# heatflow.net
KiCad netlist of a schematic drawn in EAGLE
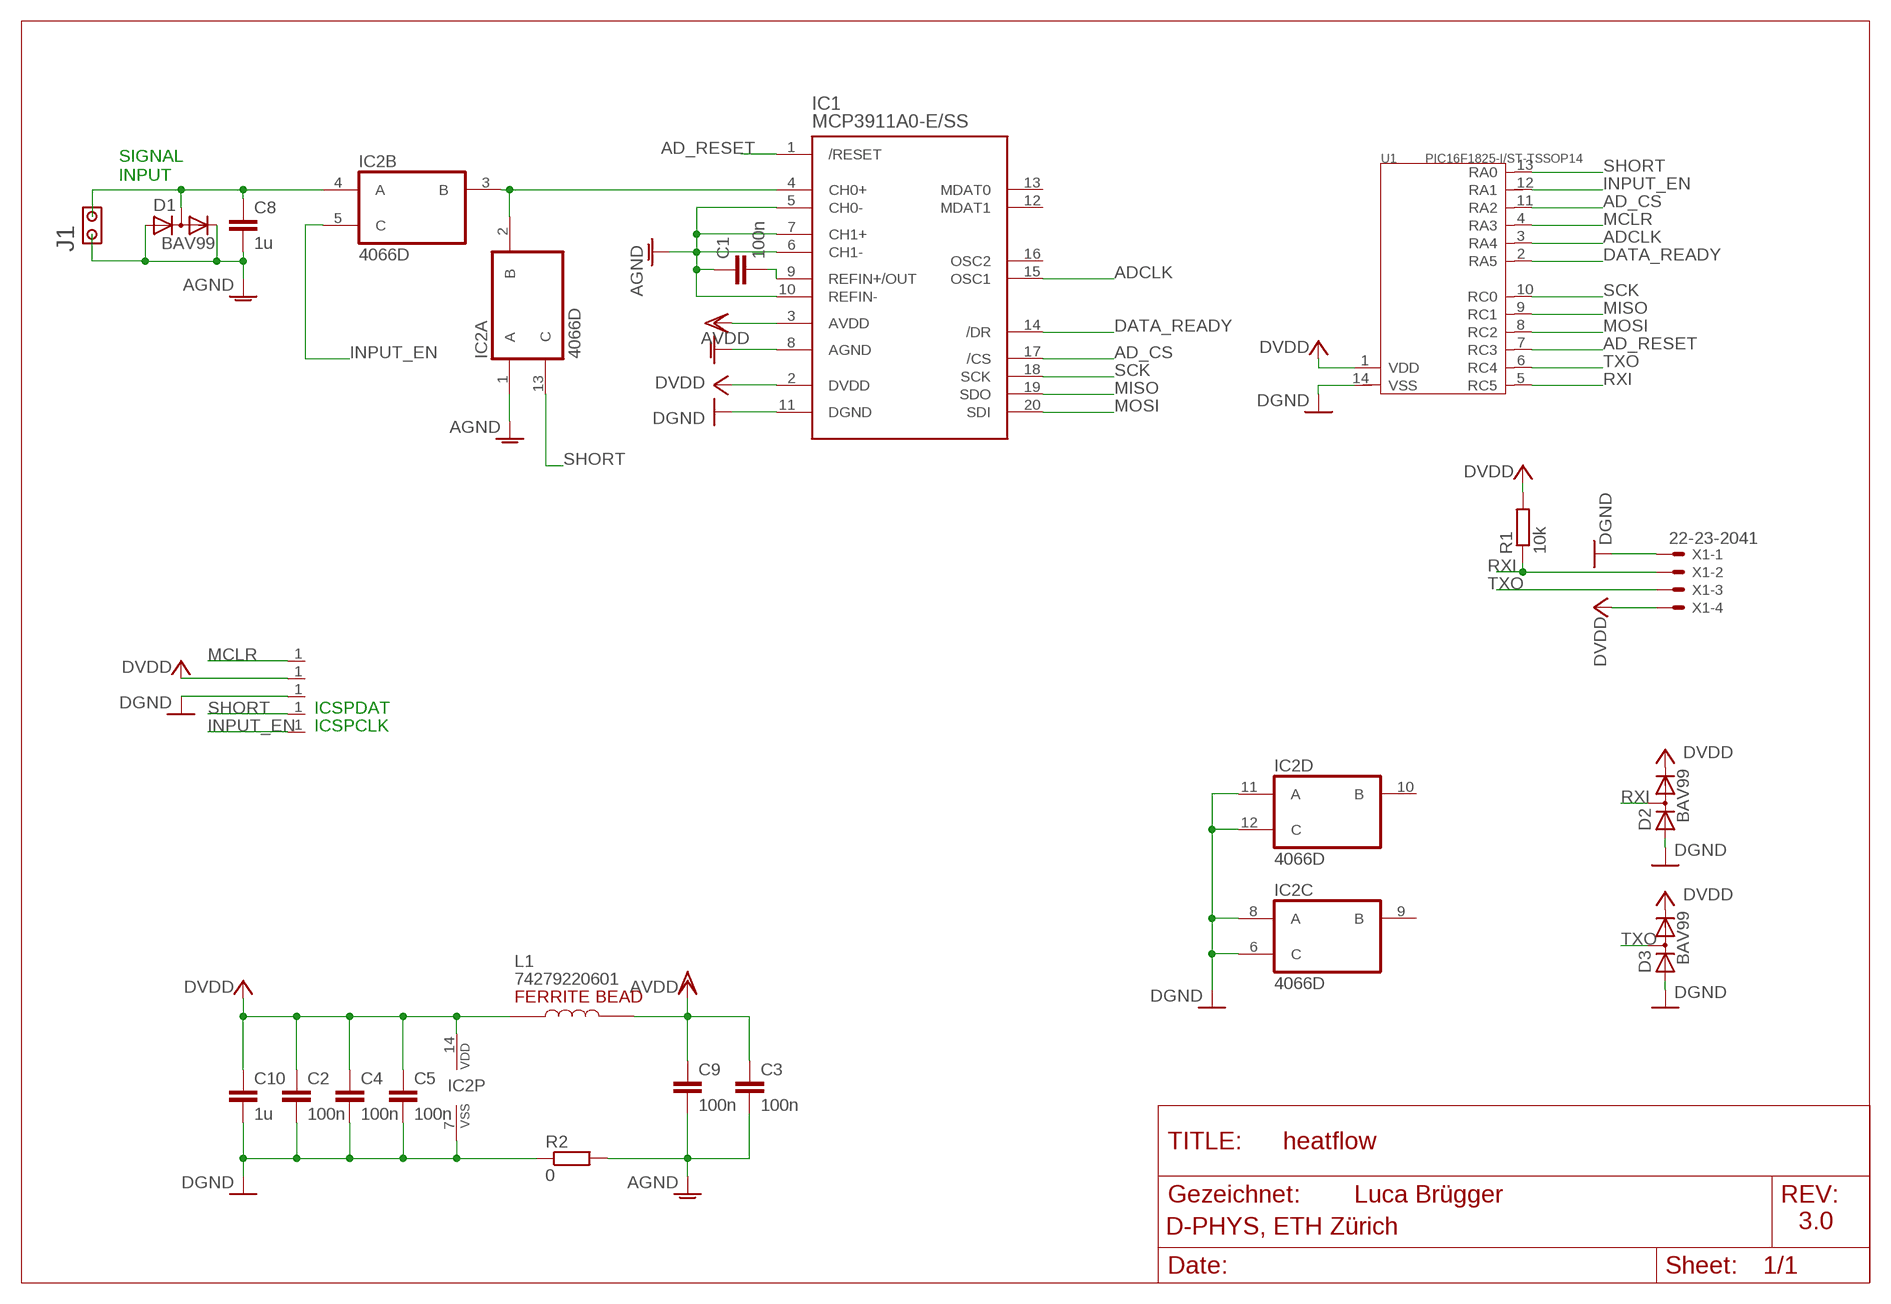
[diagram p0: schematic, sheet 1]

(export (version "E")
  (design (tool "Eeschema 10.0.6"))
  (components
    (comp (ref "C1")
      (value "100n")
      (footprint "eagle-import:C0805")
      (libsource (lib "eagle-import") (part "C-EUC0805"))
    )
    (comp (ref "C2")
      (value "100n")
      (footprint "eagle-import:C0805")
      (libsource (lib "eagle-import") (part "C-EUC0805"))
    )
    (comp (ref "C3")
      (value "100n")
      (footprint "eagle-import:C0805")
      (libsource (lib "eagle-import") (part "C-EUC0805"))
    )
    (comp (ref "C4")
      (value "100n")
      (footprint "eagle-import:C0805")
      (libsource (lib "eagle-import") (part "C-EUC0805"))
    )
    (comp (ref "C5")
      (value "100n")
      (footprint "eagle-import:C0805")
      (libsource (lib "eagle-import") (part "C-EUC0805"))
    )
    (comp (ref "C8")
      (value "1u")
      (footprint "eagle-import:C0805")
      (libsource (lib "eagle-import") (part "C-EUC0805"))
    )
    (comp (ref "C9")
      (value "100n")
      (footprint "eagle-import:C0805")
      (libsource (lib "eagle-import") (part "C-EUC0805"))
    )
    (comp (ref "C10")
      (value "1u")
      (footprint "eagle-import:C0805")
      (libsource (lib "eagle-import") (part "C-EUC0805"))
    )
    (comp (ref "D1")
      (value "BAV99")
      (footprint "eagle-import:SOT23")
      (libsource (lib "eagle-import") (part "BAV99"))
    )
    (comp (ref "D2")
      (value "BAV99")
      (footprint "eagle-import:SOT23")
      (libsource (lib "eagle-import") (part "BAV99"))
    )
    (comp (ref "D3")
      (value "BAV99")
      (footprint "eagle-import:SOT23")
      (libsource (lib "eagle-import") (part "BAV99"))
    )
    (comp (ref "IC1")
      (value "MCP3911A0-E/SS")
      (footprint "eagle-import:SSOP20")
      (libsource (lib "eagle-import") (part "MCP3911A0-E/SS"))
    )
    (comp (ref "IC2")
      (value "4066D")
      (footprint "eagle-import:SO14")
      (libsource (lib "eagle-import") (part "4066D"))
    )
    (comp (ref "J1")
      (value "CON2X1")
      (footprint "eagle-import:CON2X1")
      (libsource (lib "eagle-import") (part "CON2X1"))
    )
    (comp (ref "L1")
      (value "74279220601")
      (footprint "eagle-import:0805")
      (libsource (lib "eagle-import") (part "74279220601"))
    )
    (comp (ref "PIN1")
      (value "CON1X1")
      (footprint "eagle-import:CON1X1")
      (libsource (lib "eagle-import") (part "CON1X1"))
    )
    (comp (ref "PIN2")
      (value "CON1X1")
      (footprint "eagle-import:CON1X1")
      (libsource (lib "eagle-import") (part "CON1X1"))
    )
    (comp (ref "PIN3")
      (value "CON1X1")
      (footprint "eagle-import:CON1X1")
      (libsource (lib "eagle-import") (part "CON1X1"))
    )
    (comp (ref "PIN4")
      (value "CON1X1")
      (footprint "eagle-import:CON1X1")
      (libsource (lib "eagle-import") (part "CON1X1"))
    )
    (comp (ref "PIN5")
      (value "CON1X1")
      (footprint "eagle-import:CON1X1")
      (libsource (lib "eagle-import") (part "CON1X1"))
    )
    (comp (ref "R1")
      (value "10k")
      (footprint "eagle-import:M0805")
      (libsource (lib "eagle-import") (part "R-EU_M0805"))
    )
    (comp (ref "R2")
      (value "0")
      (footprint "eagle-import:M0805")
      (libsource (lib "eagle-import") (part "R-EU_M0805"))
    )
    (comp (ref "U1")
      (value "PIC16F1825-I/ST-TSSOP14")
      (footprint "eagle-import:TSSOP14-0.65-5X4.4MM")
      (fields (field (name "MPN") "PIC16F1825-I/ST"))
      (libsource (lib "eagle-import") (part "MCU-PIC16F1825-I/ST(TSSOP14)"))
    )
    (comp (ref "X1")
      (value "22-23-2041")
      (footprint "eagle-import:22-23-2041")
      (fields (field (name "MF") "MOLEX"))
      (libsource (lib "eagle-import") (part "22-23-2041"))
    )
  )
  (nets
    (net (code "1") (name "/ADCLK") (class "Default")
      (node (ref "IC1") (pin "15") (pinfunction "OSC1_15") (pintype "bidirectional"))
      (node (ref "U1") (pin "3") (pinfunction "RA4_3") (pintype "bidirectional"))
    )
    (net (code "2") (name "/AD_CS") (class "Default")
      (node (ref "IC1") (pin "17") (pinfunction "/CS_17") (pintype "bidirectional"))
      (node (ref "U1") (pin "11") (pinfunction "RA2_11") (pintype "bidirectional"))
    )
    (net (code "3") (name "/AD_RESET") (class "Default")
      (node (ref "IC1") (pin "1") (pinfunction "/RESET_1") (pintype "bidirectional"))
      (node (ref "U1") (pin "7") (pinfunction "RC3_7") (pintype "bidirectional"))
    )
    (net (code "4") (name "/DATA_READY") (class "Default")
      (node (ref "IC1") (pin "14") (pinfunction "/DR_14") (pintype "bidirectional"))
      (node (ref "U1") (pin "2") (pinfunction "RA5_2") (pintype "bidirectional"))
    )
    (net (code "5") (name "/INPUT_EN") (class "Default")
      (node (ref "IC2") (pin "5") (pinfunction "C_5") (pintype "input"))
      (node (ref "PIN5") (pin "1") (pinfunction "1_1") (pintype "passive"))
      (node (ref "U1") (pin "12") (pinfunction "RA1_12") (pintype "bidirectional"))
    )
    (net (code "6") (name "/MCLR") (class "Default")
      (node (ref "PIN1") (pin "1") (pinfunction "1_1") (pintype "passive"))
      (node (ref "U1") (pin "4") (pinfunction "RA3_4") (pintype "bidirectional"))
    )
    (net (code "7") (name "/MISO") (class "Default")
      (node (ref "IC1") (pin "19") (pinfunction "SDO_19") (pintype "bidirectional"))
      (node (ref "U1") (pin "9") (pinfunction "RC1_9") (pintype "bidirectional"))
    )
    (net (code "8") (name "/MOSI") (class "Default")
      (node (ref "IC1") (pin "20") (pinfunction "SDI_20") (pintype "bidirectional"))
      (node (ref "U1") (pin "8") (pinfunction "RC2_8") (pintype "bidirectional"))
    )
    (net (code "9") (name "/RXI") (class "Default")
      (node (ref "D2") (pin "3") (pinfunction "AC_3") (pintype "passive"))
      (node (ref "R1") (pin "1") (pinfunction "1_1") (pintype "passive"))
      (node (ref "U1") (pin "5") (pinfunction "RC5_5") (pintype "bidirectional"))
      (node (ref "X1") (pin "2") (pinfunction "S_2") (pintype "passive"))
    )
    (net (code "10") (name "/SCK") (class "Default")
      (node (ref "IC1") (pin "18") (pinfunction "SCK_18") (pintype "bidirectional"))
      (node (ref "U1") (pin "10") (pinfunction "RC0_10") (pintype "bidirectional"))
    )
    (net (code "11") (name "/SHORT") (class "Default")
      (node (ref "IC2") (pin "13") (pinfunction "C_13") (pintype "input"))
      (node (ref "PIN4") (pin "1") (pinfunction "1_1") (pintype "passive"))
      (node (ref "U1") (pin "13") (pinfunction "RA0_13") (pintype "bidirectional"))
    )
    (net (code "12") (name "/TXO") (class "Default")
      (node (ref "D3") (pin "3") (pinfunction "AC_3") (pintype "passive"))
      (node (ref "U1") (pin "6") (pinfunction "RC4_6") (pintype "bidirectional"))
      (node (ref "X1") (pin "3") (pinfunction "S_3") (pintype "passive"))
    )
    (net (code "13") (name "AGND") (class "Default")
      (node (ref "C1") (pin "1") (pinfunction "1_1") (pintype "passive"))
      (node (ref "C3") (pin "2") (pinfunction "2_2") (pintype "passive"))
      (node (ref "C8") (pin "2") (pinfunction "2_2") (pintype "passive"))
      (node (ref "C9") (pin "2") (pinfunction "2_2") (pintype "passive"))
      (node (ref "D1") (pin "1") (pinfunction "A_1") (pintype "passive"))
      (node (ref "D1") (pin "2") (pinfunction "C_2") (pintype "passive"))
      (node (ref "IC1") (pin "10") (pinfunction "REFIN-_10") (pintype "bidirectional"))
      (node (ref "IC1") (pin "5") (pinfunction "CH0-_5") (pintype "bidirectional"))
      (node (ref "IC1") (pin "6") (pinfunction "CH1-_6") (pintype "bidirectional"))
      (node (ref "IC1") (pin "7") (pinfunction "CH1+_7") (pintype "bidirectional"))
      (node (ref "IC1") (pin "8") (pinfunction "AGND_8") (pintype "bidirectional"))
      (node (ref "IC2") (pin "1") (pinfunction "A_1") (pintype "tri_state"))
      (node (ref "J1") (pin "1") (pinfunction "1_1") (pintype "input"))
      (node (ref "R2") (pin "2") (pinfunction "2_2") (pintype "passive"))
    )
    (net (code "14") (name "AVDD") (class "Default")
      (node (ref "C3") (pin "1") (pinfunction "1_1") (pintype "passive"))
      (node (ref "C9") (pin "1") (pinfunction "1_1") (pintype "passive"))
      (node (ref "IC1") (pin "3") (pinfunction "AVDD_3") (pintype "bidirectional"))
      (node (ref "L1") (pin "2") (pinfunction "P$2_2") (pintype "bidirectional"))
    )
    (net (code "15") (name "DGND") (class "Default")
      (node (ref "C10") (pin "2") (pinfunction "2_2") (pintype "passive"))
      (node (ref "C2") (pin "2") (pinfunction "2_2") (pintype "passive"))
      (node (ref "C4") (pin "2") (pinfunction "2_2") (pintype "passive"))
      (node (ref "C5") (pin "2") (pinfunction "2_2") (pintype "passive"))
      (node (ref "D2") (pin "1") (pinfunction "A_1") (pintype "passive"))
      (node (ref "D3") (pin "1") (pinfunction "A_1") (pintype "passive"))
      (node (ref "IC1") (pin "11") (pinfunction "DGND_11") (pintype "bidirectional"))
      (node (ref "IC2") (pin "11") (pinfunction "A_11") (pintype "tri_state"))
      (node (ref "IC2") (pin "12") (pinfunction "C_12") (pintype "input"))
      (node (ref "IC2") (pin "6") (pinfunction "C_6") (pintype "input"))
      (node (ref "IC2") (pin "7") (pinfunction "VSS_7") (pintype "power_in"))
      (node (ref "IC2") (pin "8") (pinfunction "A_8") (pintype "tri_state"))
      (node (ref "PIN3") (pin "1") (pinfunction "1_1") (pintype "passive"))
      (node (ref "R2") (pin "1") (pinfunction "1_1") (pintype "passive"))
      (node (ref "U1") (pin "14") (pinfunction "VSS_14") (pintype "bidirectional"))
      (node (ref "X1") (pin "1") (pinfunction "S_1") (pintype "passive"))
    )
    (net (code "16") (name "DVDD") (class "Default")
      (node (ref "C10") (pin "1") (pinfunction "1_1") (pintype "passive"))
      (node (ref "C2") (pin "1") (pinfunction "1_1") (pintype "passive"))
      (node (ref "C4") (pin "1") (pinfunction "1_1") (pintype "passive"))
      (node (ref "C5") (pin "1") (pinfunction "1_1") (pintype "passive"))
      (node (ref "D2") (pin "2") (pinfunction "C_2") (pintype "passive"))
      (node (ref "D3") (pin "2") (pinfunction "C_2") (pintype "passive"))
      (node (ref "IC1") (pin "2") (pinfunction "DVDD_2") (pintype "bidirectional"))
      (node (ref "IC2") (pin "14") (pinfunction "VDD_14") (pintype "power_in"))
      (node (ref "L1") (pin "1") (pinfunction "P$1_1") (pintype "bidirectional"))
      (node (ref "PIN2") (pin "1") (pinfunction "1_1") (pintype "passive"))
      (node (ref "R1") (pin "2") (pinfunction "2_2") (pintype "passive"))
      (node (ref "U1") (pin "1") (pinfunction "VDD_1") (pintype "bidirectional"))
      (node (ref "X1") (pin "4") (pinfunction "S_4") (pintype "passive"))
    )
    (net (code "17") (name "Net-(D1-AC)") (class "Default")
      (node (ref "C8") (pin "1") (pinfunction "1_1") (pintype "passive"))
      (node (ref "D1") (pin "3") (pinfunction "AC_3") (pintype "passive"))
      (node (ref "IC2") (pin "4") (pinfunction "A_4") (pintype "tri_state"))
      (node (ref "J1") (pin "2") (pinfunction "2_2") (pintype "input"))
    )
    (net (code "18") (name "Net-(IC1-CH0+)") (class "Default")
      (node (ref "IC1") (pin "4") (pinfunction "CH0+_4") (pintype "bidirectional"))
      (node (ref "IC2") (pin "2") (pinfunction "B_2") (pintype "tri_state"))
      (node (ref "IC2") (pin "3") (pinfunction "B_3") (pintype "tri_state"))
    )
    (net (code "19") (name "Net-(IC1-REFIN+{slash}OUT)") (class "Default")
      (node (ref "C1") (pin "2") (pinfunction "2_2") (pintype "passive"))
      (node (ref "IC1") (pin "9") (pinfunction "REFIN+/OUT_9") (pintype "bidirectional"))
    )
    (net (code "20") (name "unconnected-(IC1-MDAT0-Pad13)") (class "Default")
      (node (ref "IC1") (pin "13") (pinfunction "MDAT0_13") (pintype "bidirectional"))
    )
    (net (code "21") (name "unconnected-(IC1-MDAT1-Pad12)") (class "Default")
      (node (ref "IC1") (pin "12") (pinfunction "MDAT1_12") (pintype "bidirectional"))
    )
    (net (code "22") (name "unconnected-(IC1-OSC2-Pad16)") (class "Default")
      (node (ref "IC1") (pin "16") (pinfunction "OSC2_16") (pintype "bidirectional"))
    )
    (net (code "23") (name "unconnected-(IC2C-B-Pad9)") (class "Default")
      (node (ref "IC2") (pin "9") (pinfunction "B_9") (pintype "tri_state"))
    )
    (net (code "24") (name "unconnected-(IC2D-B-Pad10)") (class "Default")
      (node (ref "IC2") (pin "10") (pinfunction "B_10") (pintype "tri_state"))
    )
  )
)
